# TOF360.net
KiCad netlist of a schematic drawn in Altium Designer
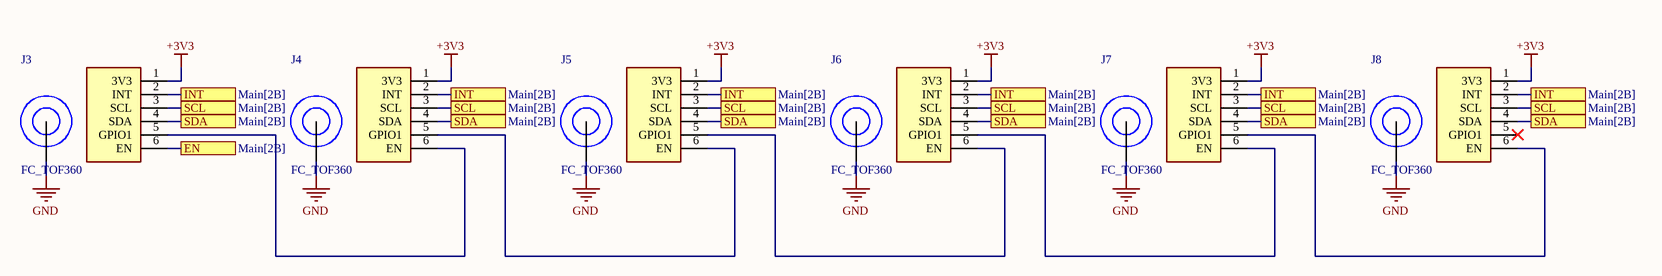
[diagram p0: TOF360.SchDoc]

(export (version "E")
  (design (tool "Eeschema 10.0.6"))
  (components
    (comp (ref "J3")
      (value "FC_TOF360")
      (footprint "SamacSys:TOF_Mount")
      (libsource (lib "SamacSys") (part "FC_TOF360"))
    )
    (comp (ref "J4")
      (value "FC_TOF360")
      (footprint "SamacSys:TOF_Mount")
      (libsource (lib "SamacSys") (part "FC_TOF360"))
    )
    (comp (ref "J5")
      (value "FC_TOF360")
      (footprint "SamacSys:TOF_Mount")
      (libsource (lib "SamacSys") (part "FC_TOF360"))
    )
    (comp (ref "J6")
      (value "FC_TOF360")
      (footprint "SamacSys:TOF_Mount")
      (libsource (lib "SamacSys") (part "FC_TOF360"))
    )
    (comp (ref "J7")
      (value "FC_TOF360")
      (footprint "SamacSys:TOF_Mount")
      (libsource (lib "SamacSys") (part "FC_TOF360"))
    )
    (comp (ref "J8")
      (value "FC_TOF360")
      (footprint "SamacSys:TOF_Mount")
      (libsource (lib "SamacSys") (part "FC_TOF360"))
    )
  )
  (nets
    (net (code "1") (name "+3V3") (class "Default")
      (node (ref "J3") (pin "1") (pinfunction "3V3_1") (pintype "passive"))
      (node (ref "J4") (pin "1") (pinfunction "3V3_1") (pintype "passive"))
      (node (ref "J5") (pin "1") (pinfunction "3V3_1") (pintype "passive"))
      (node (ref "J6") (pin "1") (pinfunction "3V3_1") (pintype "passive"))
      (node (ref "J7") (pin "1") (pinfunction "3V3_1") (pintype "passive"))
      (node (ref "J8") (pin "1") (pinfunction "3V3_1") (pintype "passive"))
    )
    (net (code "2") (name "/EN") (class "Default")
      (node (ref "J3") (pin "6") (pinfunction "EN_6") (pintype "passive"))
    )
    (net (code "3") (name "/INT") (class "Default")
      (node (ref "J3") (pin "2") (pinfunction "INT_2") (pintype "passive"))
      (node (ref "J4") (pin "2") (pinfunction "INT_2") (pintype "passive"))
      (node (ref "J5") (pin "2") (pinfunction "INT_2") (pintype "passive"))
      (node (ref "J6") (pin "2") (pinfunction "INT_2") (pintype "passive"))
      (node (ref "J7") (pin "2") (pinfunction "INT_2") (pintype "passive"))
      (node (ref "J8") (pin "2") (pinfunction "INT_2") (pintype "passive"))
    )
    (net (code "4") (name "/SCL") (class "Default")
      (node (ref "J3") (pin "3") (pinfunction "SCL_3") (pintype "passive"))
      (node (ref "J4") (pin "3") (pinfunction "SCL_3") (pintype "passive"))
      (node (ref "J5") (pin "3") (pinfunction "SCL_3") (pintype "passive"))
      (node (ref "J6") (pin "3") (pinfunction "SCL_3") (pintype "passive"))
      (node (ref "J7") (pin "3") (pinfunction "SCL_3") (pintype "passive"))
      (node (ref "J8") (pin "3") (pinfunction "SCL_3") (pintype "passive"))
    )
    (net (code "5") (name "/SDA") (class "Default")
      (node (ref "J3") (pin "4") (pinfunction "SDA_4") (pintype "passive"))
      (node (ref "J4") (pin "4") (pinfunction "SDA_4") (pintype "passive"))
      (node (ref "J5") (pin "4") (pinfunction "SDA_4") (pintype "passive"))
      (node (ref "J6") (pin "4") (pinfunction "SDA_4") (pintype "passive"))
      (node (ref "J7") (pin "4") (pinfunction "SDA_4") (pintype "passive"))
      (node (ref "J8") (pin "4") (pinfunction "SDA_4") (pintype "passive"))
    )
    (net (code "6") (name "GND") (class "Default")
      (node (ref "J3") (pin "7") (pinfunction "7_7") (pintype "passive"))
      (node (ref "J4") (pin "7") (pinfunction "7_7") (pintype "passive"))
      (node (ref "J5") (pin "7") (pinfunction "7_7") (pintype "passive"))
      (node (ref "J6") (pin "7") (pinfunction "7_7") (pintype "passive"))
      (node (ref "J7") (pin "7") (pinfunction "7_7") (pintype "passive"))
      (node (ref "J8") (pin "7") (pinfunction "7_7") (pintype "passive"))
    )
    (net (code "7") (name "Net-(J3-GPIO1)") (class "Default")
      (node (ref "J3") (pin "5") (pinfunction "GPIO1_5") (pintype "passive"))
      (node (ref "J4") (pin "6") (pinfunction "EN_6") (pintype "passive"))
    )
    (net (code "8") (name "Net-(J4-GPIO1)") (class "Default")
      (node (ref "J4") (pin "5") (pinfunction "GPIO1_5") (pintype "passive"))
      (node (ref "J5") (pin "6") (pinfunction "EN_6") (pintype "passive"))
    )
    (net (code "9") (name "Net-(J5-GPIO1)") (class "Default")
      (node (ref "J5") (pin "5") (pinfunction "GPIO1_5") (pintype "passive"))
      (node (ref "J6") (pin "6") (pinfunction "EN_6") (pintype "passive"))
    )
    (net (code "10") (name "Net-(J6-GPIO1)") (class "Default")
      (node (ref "J6") (pin "5") (pinfunction "GPIO1_5") (pintype "passive"))
      (node (ref "J7") (pin "6") (pinfunction "EN_6") (pintype "passive"))
    )
    (net (code "11") (name "Net-(J7-GPIO1)") (class "Default")
      (node (ref "J7") (pin "5") (pinfunction "GPIO1_5") (pintype "passive"))
      (node (ref "J8") (pin "6") (pinfunction "EN_6") (pintype "passive"))
    )
    (net (code "12") (name "unconnected-(J8-GPIO1-Pad5)") (class "Default")
      (node (ref "J8") (pin "5") (pinfunction "GPIO1_5") (pintype "passive+no_connect"))
    )
  )
)
